# Sheet2.net
KiCad netlist of a schematic drawn in Altium Designer
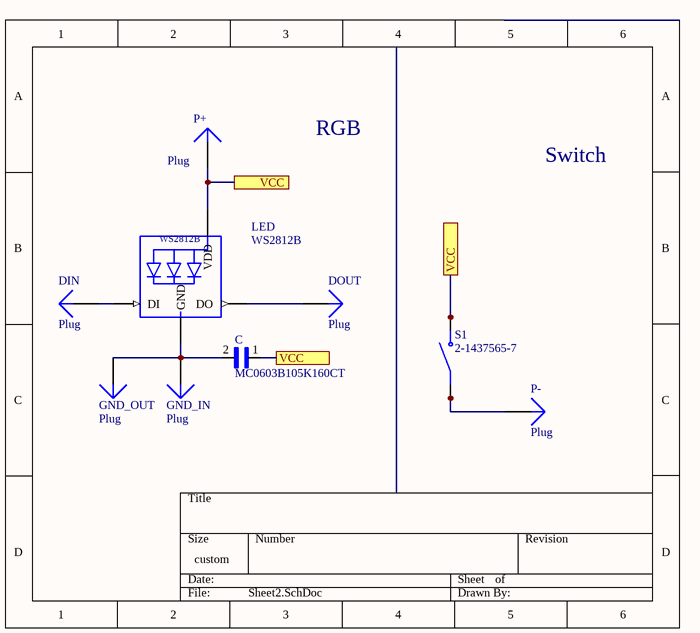
[diagram p0: Sheet2.SchDoc]

(export (version "E")
  (design (tool "Eeschema 10.0.6"))
  (components
    (comp (ref "C")
      (value "MC0603B105K160CT")
      (footprint "0603cap:CAPC1608X87N")
      (description "Cap, Mlcc, X7r, 1uf, 16v, 0603")
      (fields (field (name "MF") "Multicomp"))
      (libsource (lib "0603cap") (part "MC0603B105K160CT"))
    )
    (comp (ref "DIN")
      (value "Plug")
      (footprint "PIN1")
      (fields (field (name "PUBLISHER") "Altium Limited"))
      (libsource (lib "Miscellaneous Connectors") (part "Plug"))
    )
    (comp (ref "DOUT")
      (value "Plug")
      (footprint "PIN1")
      (fields (field (name "PUBLISHER") "Altium Limited"))
      (libsource (lib "Miscellaneous Connectors") (part "Plug"))
    )
    (comp (ref "GND_IN")
      (value "Plug")
      (footprint "PIN1")
      (fields (field (name "PUBLISHER") "Altium Limited"))
      (libsource (lib "Miscellaneous Connectors") (part "Plug"))
    )
    (comp (ref "GND_OUT")
      (value "Plug")
      (footprint "PIN1")
      (fields (field (name "PUBLISHER") "Altium Limited"))
      (libsource (lib "Miscellaneous Connectors") (part "Plug"))
    )
    (comp (ref "LED")
      (value "WS2812B")
      (footprint "LED_WS2812B-B")
      (description "Raspberry Pi HAT _40 pin_ Wheeled Robotics Kit")
      (fields (field (name "MF") "SparkFun Electronics"))
      (libsource (lib "2WS2812B") (part "WS2812B"))
    )
    (comp (ref "P+")
      (value "Plug")
      (footprint "PIN1")
      (fields (field (name "PUBLISHER") "Altium Limited"))
      (libsource (lib "Miscellaneous Connectors") (part "Plug"))
    )
    (comp (ref "P-")
      (value "Plug")
      (footprint "PIN1")
      (fields (field (name "PUBLISHER") "Altium Limited"))
      (libsource (lib "Miscellaneous Connectors") (part "Plug"))
    )
    (comp (ref "S1")
      (value "2-1437565-7")
      (footprint "Pulsador:SW_2-1437565-7")
      (description "Tactile Switch SPST-NO Top Actuated Surface Mount")
      (fields (field (name "MF") "TE Connectivity"))
      (libsource (lib "Pulsador") (part "2-1437565-7"))
    )
  )
  (nets
    (net (code "1") (name "/VCC") (class "Default")
      (node (ref "C") (pin "1") (pinfunction "1_1") (pintype "passive"))
      (node (ref "LED") (pin "1-VDD") (pinfunction "VDD_1-VDD") (pintype "power_in"))
      (node (ref "P+") (pin "1") (pinfunction "1_1") (pintype "passive"))
      (node (ref "S1") (pin "3") (pinfunction "NO_3") (pintype "passive"))
      (node (ref "S1") (pin "4") (pinfunction "NO_4") (pintype "passive"))
    )
    (net (code "2") (name "Net-(LED-DI)") (class "Default")
      (node (ref "DIN") (pin "1") (pinfunction "1_1") (pintype "passive"))
      (node (ref "LED") (pin "4-DIN") (pinfunction "DI_4-DIN") (pintype "input"))
    )
    (net (code "3") (name "Net-(LED-DO)") (class "Default")
      (node (ref "DOUT") (pin "1") (pinfunction "1_1") (pintype "passive"))
      (node (ref "LED") (pin "2-DOUT") (pinfunction "DO_2-DOUT") (pintype "output"))
    )
    (net (code "4") (name "Net-(LED-GND)") (class "Default")
      (node (ref "C") (pin "2") (pinfunction "2_2") (pintype "passive"))
      (node (ref "GND_IN") (pin "1") (pinfunction "1_1") (pintype "passive"))
      (node (ref "GND_OUT") (pin "1") (pinfunction "1_1") (pintype "passive"))
      (node (ref "LED") (pin "3-GND") (pinfunction "GND_3-GND") (pintype "power_in"))
    )
    (net (code "5") (name "Net-(P--Pad1)") (class "Default")
      (node (ref "P-") (pin "1") (pinfunction "1_1") (pintype "passive"))
      (node (ref "S1") (pin "1") (pinfunction "COM_1") (pintype "passive"))
      (node (ref "S1") (pin "2") (pinfunction "COM_2") (pintype "passive"))
    )
  )
)
